# Frienduino.net
KiCad netlist of a schematic drawn in EAGLE
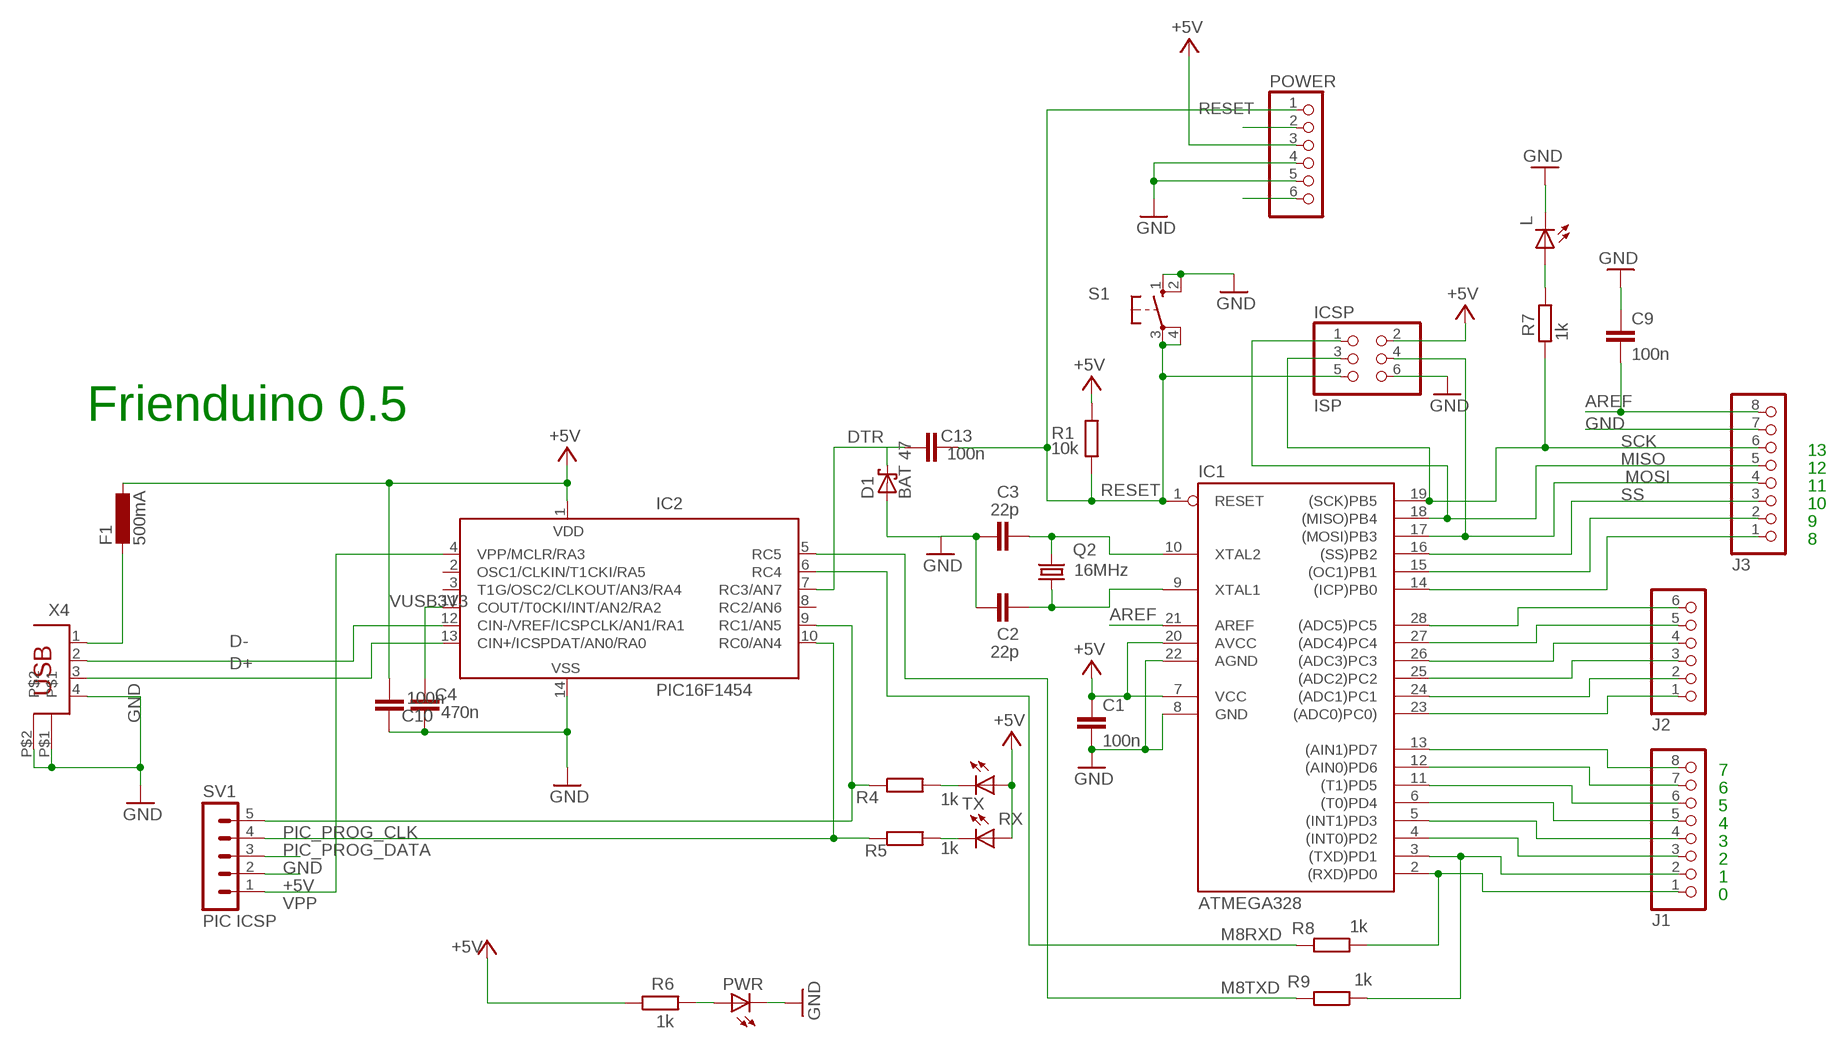
[diagram p0: schematic, sheet 1]

(export (version "E")
  (design (tool "Eeschema 10.0.6"))
  (components
    (comp (ref "C1")
      (value "100n")
      (footprint "eagle-import:C050-025X075")
      (libsource (lib "eagle-import") (part "C-EU050-025X075"))
    )
    (comp (ref "C2")
      (value "22p")
      (footprint "eagle-import:C050-024X044")
      (libsource (lib "eagle-import") (part "C-EU050-024X044"))
    )
    (comp (ref "C3")
      (value "22p")
      (footprint "eagle-import:C050-024X044")
      (libsource (lib "eagle-import") (part "C-EU050-024X044"))
    )
    (comp (ref "C4")
      (value "470n")
      (footprint "eagle-import:C050-025X075")
      (libsource (lib "eagle-import") (part "C-EU050-025X075"))
    )
    (comp (ref "C9")
      (value "100n")
      (footprint "eagle-import:C050-025X075")
      (libsource (lib "eagle-import") (part "C-EU050-025X075"))
    )
    (comp (ref "C10")
      (value "100n")
      (footprint "eagle-import:C050-025X075")
      (libsource (lib "eagle-import") (part "C-EU050-025X075"))
    )
    (comp (ref "C13")
      (value "100n")
      (footprint "eagle-import:C050-025X075")
      (libsource (lib "eagle-import") (part "C-EU050-025X075"))
    )
    (comp (ref "D1")
      (value "BAT 47")
      (footprint "eagle-import:DO35-7")
      (libsource (lib "eagle-import") (part "SCHOTTKY-DIODEDO35-7"))
    )
    (comp (ref "F1")
      (value "500mA")
      (footprint "eagle-import:0204_5")
      (libsource (lib "eagle-import") (part "L-EU0204/5"))
    )
    (comp (ref "IC1")
      (value "ATMEGA328")
      (footprint "eagle-import:DIL28-3")
      (libsource (lib "eagle-import") (part "AT90S4433P"))
    )
    (comp (ref "IC2")
      (value "PIC16F1454")
      (footprint "eagle-import:DIL14")
      (fields (field (name "MF") "MICROCHIP") (field (name "MPN") "PIC16F676-I/P"))
      (libsource (lib "eagle-import") (part "PIC16F676P"))
    )
    (comp (ref "ICSP")
      (value "ISP")
      (footprint "eagle-import:2X03")
      (libsource (lib "eagle-import") (part "PINHD-2X3"))
    )
    (comp (ref "J1")
      (value "PINHD-1X8")
      (footprint "eagle-import:1X08")
      (libsource (lib "eagle-import") (part "PINHD-1X8"))
    )
    (comp (ref "J2")
      (value "PINHD-1X6")
      (footprint "eagle-import:1X06")
      (libsource (lib "eagle-import") (part "PINHD-1X6"))
    )
    (comp (ref "J3")
      (value "PINHD-1X8")
      (footprint "eagle-import:1X08")
      (libsource (lib "eagle-import") (part "PINHD-1X8"))
    )
    (comp (ref "L")
      (value "LED3MM")
      (footprint "eagle-import:LED3MM")
      (libsource (lib "eagle-import") (part "LED3MM"))
    )
    (comp (ref "POWER")
      (value "PINHD-1X6")
      (footprint "eagle-import:1X06")
      (libsource (lib "eagle-import") (part "PINHD-1X6"))
    )
    (comp (ref "PWR")
      (value "LED3MM")
      (footprint "eagle-import:LED3MM")
      (libsource (lib "eagle-import") (part "LED3MM"))
    )
    (comp (ref "Q2")
      (value "16MHz")
      (footprint "eagle-import:HC49_S")
      (libsource (lib "eagle-import") (part "CRYTALHC49S"))
    )
    (comp (ref "R1")
      (value "10k")
      (footprint "eagle-import:0204_7")
      (libsource (lib "eagle-import") (part "R-EU_0204/7"))
    )
    (comp (ref "R4")
      (value "1k")
      (footprint "eagle-import:0204_7")
      (libsource (lib "eagle-import") (part "R-EU_0204/7"))
    )
    (comp (ref "R5")
      (value "1k")
      (footprint "eagle-import:0204_7")
      (libsource (lib "eagle-import") (part "R-EU_0204/7"))
    )
    (comp (ref "R6")
      (value "1k")
      (footprint "eagle-import:0204_7")
      (libsource (lib "eagle-import") (part "R-EU_0204/7"))
    )
    (comp (ref "R7")
      (value "1k")
      (footprint "eagle-import:0204_7")
      (libsource (lib "eagle-import") (part "R-EU_0204/7"))
    )
    (comp (ref "R8")
      (value "1k")
      (footprint "eagle-import:0204_7")
      (libsource (lib "eagle-import") (part "R-EU_0204/7"))
    )
    (comp (ref "R9")
      (value "1k")
      (footprint "eagle-import:0204_7")
      (libsource (lib "eagle-import") (part "R-EU_0204/7"))
    )
    (comp (ref "RX")
      (value "LED3MM")
      (footprint "eagle-import:LED3MM")
      (libsource (lib "eagle-import") (part "LED3MM"))
    )
    (comp (ref "S1")
      (value "10-XX")
      (footprint "eagle-import:B3F-10XX")
      (libsource (lib "eagle-import") (part "10-XX"))
    )
    (comp (ref "SV1")
      (value "PIC ICSP")
      (footprint "eagle-import:MA05-1")
      (libsource (lib "eagle-import") (part "MA05-1"))
    )
    (comp (ref "TX")
      (value "LED3MM")
      (footprint "eagle-import:LED3MM")
      (libsource (lib "eagle-import") (part "LED3MM"))
    )
    (comp (ref "X4")
      (value "PN61729")
      (footprint "eagle-import:PN61729")
      (libsource (lib "eagle-import") (part "PN61729"))
    )
  )
  (nets
    (net (code "1") (name "+5V") (class "Default")
      (node (ref "C1") (pin "1") (pinfunction "1_1") (pintype "passive"))
      (node (ref "C10") (pin "1") (pinfunction "1_1") (pintype "passive"))
      (node (ref "F1") (pin "1") (pinfunction "1_1") (pintype "passive"))
      (node (ref "IC1") (pin "20") (pinfunction "AVCC_20") (pintype "power_in"))
      (node (ref "IC1") (pin "7") (pinfunction "VCC_7") (pintype "power_in"))
      (node (ref "IC2") (pin "1") (pinfunction "VDD_1") (pintype "power_in"))
      (node (ref "ICSP") (pin "2") (pinfunction "2_2") (pintype "passive"))
      (node (ref "POWER") (pin "3") (pinfunction "3_3") (pintype "passive"))
      (node (ref "R1") (pin "2") (pinfunction "2_2") (pintype "passive"))
      (node (ref "R6") (pin "1") (pinfunction "1_1") (pintype "passive"))
      (node (ref "RX") (pin "A") (pinfunction "A_A") (pintype "passive"))
      (node (ref "SV1") (pin "2") (pinfunction "2_2") (pintype "passive"))
      (node (ref "TX") (pin "A") (pinfunction "A_A") (pintype "passive"))
    )
    (net (code "2") (name "/AREF") (class "Default")
      (node (ref "C9") (pin "2") (pinfunction "2_2") (pintype "passive"))
      (node (ref "IC1") (pin "21") (pinfunction "AREF_21") (pintype "power_in"))
      (node (ref "J3") (pin "8") (pinfunction "8_8") (pintype "passive"))
    )
    (net (code "3") (name "/D+") (class "Default")
      (node (ref "IC2") (pin "13") (pinfunction "CIN+/ICSPDAT/AN0/RA0_13") (pintype "bidirectional"))
      (node (ref "X4") (pin "3") (pinfunction "3_3") (pintype "bidirectional"))
    )
    (net (code "4") (name "/D-") (class "Default")
      (node (ref "IC2") (pin "12") (pinfunction "CIN-/VREF/ICSPCLK/AN1/RA1_12") (pintype "bidirectional"))
      (node (ref "X4") (pin "2") (pinfunction "2_2") (pintype "bidirectional"))
    )
    (net (code "5") (name "/DTR") (class "Default")
      (node (ref "C13") (pin "1") (pinfunction "1_1") (pintype "passive"))
      (node (ref "D1") (pin "C") (pinfunction "C_C") (pintype "passive"))
      (node (ref "IC2") (pin "7") (pinfunction "RC3/AN7_7") (pintype "bidirectional"))
    )
    (net (code "6") (name "/M8RXD") (class "Default")
      (node (ref "IC2") (pin "6") (pinfunction "RC4_6") (pintype "bidirectional"))
      (node (ref "R8") (pin "2") (pinfunction "2_2") (pintype "passive"))
    )
    (net (code "7") (name "/M8TXD") (class "Default")
      (node (ref "IC2") (pin "5") (pinfunction "RC5_5") (pintype "bidirectional"))
      (node (ref "R9") (pin "2") (pinfunction "2_2") (pintype "passive"))
    )
    (net (code "8") (name "/MISO") (class "Default")
      (node (ref "IC1") (pin "18") (pinfunction "(MISO)PB4_18") (pintype "bidirectional"))
      (node (ref "ICSP") (pin "1") (pinfunction "1_1") (pintype "passive"))
      (node (ref "J3") (pin "5") (pinfunction "5_5") (pintype "passive"))
    )
    (net (code "9") (name "/MOSI") (class "Default")
      (node (ref "IC1") (pin "17") (pinfunction "(MOSI)PB3_17") (pintype "bidirectional"))
      (node (ref "ICSP") (pin "4") (pinfunction "4_4") (pintype "passive"))
      (node (ref "J3") (pin "4") (pinfunction "4_4") (pintype "passive"))
    )
    (net (code "10") (name "/PIC_PROG_CLK") (class "Default")
      (node (ref "IC2") (pin "9") (pinfunction "RC1/AN5_9") (pintype "bidirectional"))
      (node (ref "R4") (pin "1") (pinfunction "1_1") (pintype "passive"))
      (node (ref "SV1") (pin "5") (pinfunction "5_5") (pintype "passive"))
    )
    (net (code "11") (name "/PIC_PROG_DATA") (class "Default")
      (node (ref "IC2") (pin "10") (pinfunction "RC0/AN4_10") (pintype "bidirectional"))
      (node (ref "R5") (pin "1") (pinfunction "1_1") (pintype "passive"))
      (node (ref "SV1") (pin "4") (pinfunction "4_4") (pintype "passive"))
    )
    (net (code "12") (name "/RESET") (class "Default")
      (node (ref "C13") (pin "2") (pinfunction "2_2") (pintype "passive"))
      (node (ref "IC1") (pin "1") (pinfunction "RESET_1") (pintype "input"))
      (node (ref "ICSP") (pin "5") (pinfunction "5_5") (pintype "passive"))
      (node (ref "POWER") (pin "1") (pinfunction "1_1") (pintype "passive"))
      (node (ref "R1") (pin "1") (pinfunction "1_1") (pintype "passive"))
      (node (ref "S1") (pin "3") (pinfunction "P_3") (pintype "passive"))
      (node (ref "S1") (pin "4") (pinfunction "P1_4") (pintype "passive"))
    )
    (net (code "13") (name "/SCK") (class "Default")
      (node (ref "IC1") (pin "19") (pinfunction "(SCK)PB5_19") (pintype "bidirectional"))
      (node (ref "ICSP") (pin "3") (pinfunction "3_3") (pintype "passive"))
      (node (ref "J3") (pin "6") (pinfunction "6_6") (pintype "passive"))
      (node (ref "R7") (pin "2") (pinfunction "2_2") (pintype "passive"))
    )
    (net (code "14") (name "/SS") (class "Default")
      (node (ref "IC1") (pin "16") (pinfunction "(SS)PB2_16") (pintype "bidirectional"))
      (node (ref "J3") (pin "3") (pinfunction "3_3") (pintype "passive"))
    )
    (net (code "15") (name "/VPP") (class "Default")
      (node (ref "IC2") (pin "4") (pinfunction "VPP/MCLR/RA3_4") (pintype "input"))
      (node (ref "SV1") (pin "1") (pinfunction "1_1") (pintype "passive"))
    )
    (net (code "16") (name "/VUSB3V3") (class "Default")
      (node (ref "C4") (pin "2") (pinfunction "2_2") (pintype "passive"))
      (node (ref "IC2") (pin "11") (pinfunction "COUT/T0CKI/INT/AN2/RA2_11") (pintype "bidirectional"))
    )
    (net (code "17") (name "GND") (class "Default")
      (node (ref "C1") (pin "2") (pinfunction "2_2") (pintype "passive"))
      (node (ref "C10") (pin "2") (pinfunction "2_2") (pintype "passive"))
      (node (ref "C2") (pin "1") (pinfunction "1_1") (pintype "passive"))
      (node (ref "C3") (pin "1") (pinfunction "1_1") (pintype "passive"))
      (node (ref "C4") (pin "1") (pinfunction "1_1") (pintype "passive"))
      (node (ref "C9") (pin "1") (pinfunction "1_1") (pintype "passive"))
      (node (ref "D1") (pin "A") (pinfunction "A_A") (pintype "passive"))
      (node (ref "IC1") (pin "22") (pinfunction "AGND_22") (pintype "power_in"))
      (node (ref "IC1") (pin "8") (pinfunction "GND_8") (pintype "power_in"))
      (node (ref "IC2") (pin "14") (pinfunction "VSS_14") (pintype "power_in"))
      (node (ref "ICSP") (pin "6") (pinfunction "6_6") (pintype "passive"))
      (node (ref "J3") (pin "7") (pinfunction "7_7") (pintype "passive"))
      (node (ref "L") (pin "K") (pinfunction "C_K") (pintype "passive"))
      (node (ref "POWER") (pin "4") (pinfunction "4_4") (pintype "passive"))
      (node (ref "POWER") (pin "5") (pinfunction "5_5") (pintype "passive"))
      (node (ref "PWR") (pin "K") (pinfunction "C_K") (pintype "passive"))
      (node (ref "S1") (pin "1") (pinfunction "S_1") (pintype "passive"))
      (node (ref "S1") (pin "2") (pinfunction "S1_2") (pintype "passive"))
      (node (ref "SV1") (pin "3") (pinfunction "3_3") (pintype "passive"))
      (node (ref "X4") (pin "4") (pinfunction "4_4") (pintype "bidirectional"))
      (node (ref "X4") (pin "P$1") (pinfunction "P$1_P$1") (pintype "bidirectional"))
      (node (ref "X4") (pin "P$2") (pinfunction "P$2_P$2") (pintype "bidirectional"))
    )
    (net (code "18") (name "Net-(F1-Pad2)") (class "Default")
      (node (ref "F1") (pin "2") (pinfunction "2_2") (pintype "passive"))
      (node (ref "X4") (pin "1") (pinfunction "1_1") (pintype "bidirectional"))
    )
    (net (code "19") (name "Net-(IC1-(ADC0)PC0))") (class "Default")
      (node (ref "IC1") (pin "23") (pinfunction "(ADC0)PC0)_23") (pintype "bidirectional"))
      (node (ref "J2") (pin "1") (pinfunction "1_1") (pintype "passive"))
    )
    (net (code "20") (name "Net-(IC1-(ADC1)PC1)") (class "Default")
      (node (ref "IC1") (pin "24") (pinfunction "(ADC1)PC1_24") (pintype "bidirectional"))
      (node (ref "J2") (pin "2") (pinfunction "2_2") (pintype "passive"))
    )
    (net (code "21") (name "Net-(IC1-(ADC2)PC2)") (class "Default")
      (node (ref "IC1") (pin "25") (pinfunction "(ADC2)PC2_25") (pintype "bidirectional"))
      (node (ref "J2") (pin "3") (pinfunction "3_3") (pintype "passive"))
    )
    (net (code "22") (name "Net-(IC1-(ADC3)PC3)") (class "Default")
      (node (ref "IC1") (pin "26") (pinfunction "(ADC3)PC3_26") (pintype "bidirectional"))
      (node (ref "J2") (pin "4") (pinfunction "4_4") (pintype "passive"))
    )
    (net (code "23") (name "Net-(IC1-(ADC4)PC4)") (class "Default")
      (node (ref "IC1") (pin "27") (pinfunction "(ADC4)PC4_27") (pintype "bidirectional"))
      (node (ref "J2") (pin "5") (pinfunction "5_5") (pintype "passive"))
    )
    (net (code "24") (name "Net-(IC1-(ADC5)PC5)") (class "Default")
      (node (ref "IC1") (pin "28") (pinfunction "(ADC5)PC5_28") (pintype "bidirectional"))
      (node (ref "J2") (pin "6") (pinfunction "6_6") (pintype "passive"))
    )
    (net (code "25") (name "Net-(IC1-(AIN0)PD6)") (class "Default")
      (node (ref "IC1") (pin "12") (pinfunction "(AIN0)PD6_12") (pintype "bidirectional"))
      (node (ref "J1") (pin "7") (pinfunction "7_7") (pintype "passive"))
    )
    (net (code "26") (name "Net-(IC1-(AIN1)PD7)") (class "Default")
      (node (ref "IC1") (pin "13") (pinfunction "(AIN1)PD7_13") (pintype "bidirectional"))
      (node (ref "J1") (pin "8") (pinfunction "8_8") (pintype "passive"))
    )
    (net (code "27") (name "Net-(IC1-(ICP)PB0)") (class "Default")
      (node (ref "IC1") (pin "14") (pinfunction "(ICP)PB0_14") (pintype "bidirectional"))
      (node (ref "J3") (pin "1") (pinfunction "1_1") (pintype "passive"))
    )
    (net (code "28") (name "Net-(IC1-(INT0)PD2)") (class "Default")
      (node (ref "IC1") (pin "4") (pinfunction "(INT0)PD2_4") (pintype "bidirectional"))
      (node (ref "J1") (pin "3") (pinfunction "3_3") (pintype "passive"))
    )
    (net (code "29") (name "Net-(IC1-(INT1)PD3)") (class "Default")
      (node (ref "IC1") (pin "5") (pinfunction "(INT1)PD3_5") (pintype "bidirectional"))
      (node (ref "J1") (pin "4") (pinfunction "4_4") (pintype "passive"))
    )
    (net (code "30") (name "Net-(IC1-(OC1)PB1)") (class "Default")
      (node (ref "IC1") (pin "15") (pinfunction "(OC1)PB1_15") (pintype "bidirectional"))
      (node (ref "J3") (pin "2") (pinfunction "2_2") (pintype "passive"))
    )
    (net (code "31") (name "Net-(IC1-(RXD)PD0)") (class "Default")
      (node (ref "IC1") (pin "2") (pinfunction "(RXD)PD0_2") (pintype "bidirectional"))
      (node (ref "J1") (pin "1") (pinfunction "1_1") (pintype "passive"))
      (node (ref "R8") (pin "1") (pinfunction "1_1") (pintype "passive"))
    )
    (net (code "32") (name "Net-(IC1-(T0)PD4)") (class "Default")
      (node (ref "IC1") (pin "6") (pinfunction "(T0)PD4_6") (pintype "bidirectional"))
      (node (ref "J1") (pin "5") (pinfunction "5_5") (pintype "passive"))
    )
    (net (code "33") (name "Net-(IC1-(T1)PD5)") (class "Default")
      (node (ref "IC1") (pin "11") (pinfunction "(T1)PD5_11") (pintype "bidirectional"))
      (node (ref "J1") (pin "6") (pinfunction "6_6") (pintype "passive"))
    )
    (net (code "34") (name "Net-(IC1-(TXD)PD1)") (class "Default")
      (node (ref "IC1") (pin "3") (pinfunction "(TXD)PD1_3") (pintype "bidirectional"))
      (node (ref "J1") (pin "2") (pinfunction "2_2") (pintype "passive"))
      (node (ref "R9") (pin "1") (pinfunction "1_1") (pintype "passive"))
    )
    (net (code "35") (name "Net-(IC1-XTAL1)") (class "Default")
      (node (ref "C2") (pin "2") (pinfunction "2_2") (pintype "passive"))
      (node (ref "IC1") (pin "9") (pinfunction "XTAL1_9") (pintype "bidirectional"))
      (node (ref "Q2") (pin "1") (pinfunction "1_1") (pintype "passive"))
    )
    (net (code "36") (name "Net-(IC1-XTAL2)") (class "Default")
      (node (ref "C3") (pin "2") (pinfunction "2_2") (pintype "passive"))
      (node (ref "IC1") (pin "10") (pinfunction "XTAL2_10") (pintype "bidirectional"))
      (node (ref "Q2") (pin "2") (pinfunction "2_2") (pintype "passive"))
    )
    (net (code "37") (name "Net-(L-PadA)") (class "Default")
      (node (ref "L") (pin "A") (pinfunction "A_A") (pintype "passive"))
      (node (ref "R7") (pin "1") (pinfunction "1_1") (pintype "passive"))
    )
    (net (code "38") (name "Net-(PWR-PadA)") (class "Default")
      (node (ref "PWR") (pin "A") (pinfunction "A_A") (pintype "passive"))
      (node (ref "R6") (pin "2") (pinfunction "2_2") (pintype "passive"))
    )
    (net (code "39") (name "Net-(RX-C)") (class "Default")
      (node (ref "R5") (pin "2") (pinfunction "2_2") (pintype "passive"))
      (node (ref "RX") (pin "K") (pinfunction "C_K") (pintype "passive"))
    )
    (net (code "40") (name "Net-(TX-C)") (class "Default")
      (node (ref "R4") (pin "2") (pinfunction "2_2") (pintype "passive"))
      (node (ref "TX") (pin "K") (pinfunction "C_K") (pintype "passive"))
    )
    (net (code "41") (name "unconnected-(IC2-OSC1{slash}CLKIN{slash}T1CKI{slash}RA5-Pad2)") (class "Default")
      (node (ref "IC2") (pin "2") (pinfunction "OSC1/CLKIN/T1CKI/RA5_2") (pintype "bidirectional"))
    )
    (net (code "42") (name "unconnected-(IC2-RC2{slash}AN6-Pad8)") (class "Default")
      (node (ref "IC2") (pin "8") (pinfunction "RC2/AN6_8") (pintype "bidirectional"))
    )
    (net (code "43") (name "unconnected-(IC2-T1G{slash}OSC2{slash}CLKOUT{slash}AN3{slash}RA4-Pad3)") (class "Default")
      (node (ref "IC2") (pin "3") (pinfunction "T1G/OSC2/CLKOUT/AN3/RA4_3") (pintype "bidirectional"))
    )
    (net (code "44") (name "unconnected-(POWER-Pad2)") (class "Default")
      (node (ref "POWER") (pin "2") (pinfunction "2_2") (pintype "passive"))
    )
    (net (code "45") (name "unconnected-(POWER-Pad6)") (class "Default")
      (node (ref "POWER") (pin "6") (pinfunction "6_6") (pintype "passive"))
    )
  )
)
